# hv-supply.net
KiCad netlist of a schematic drawn in Altium Designer
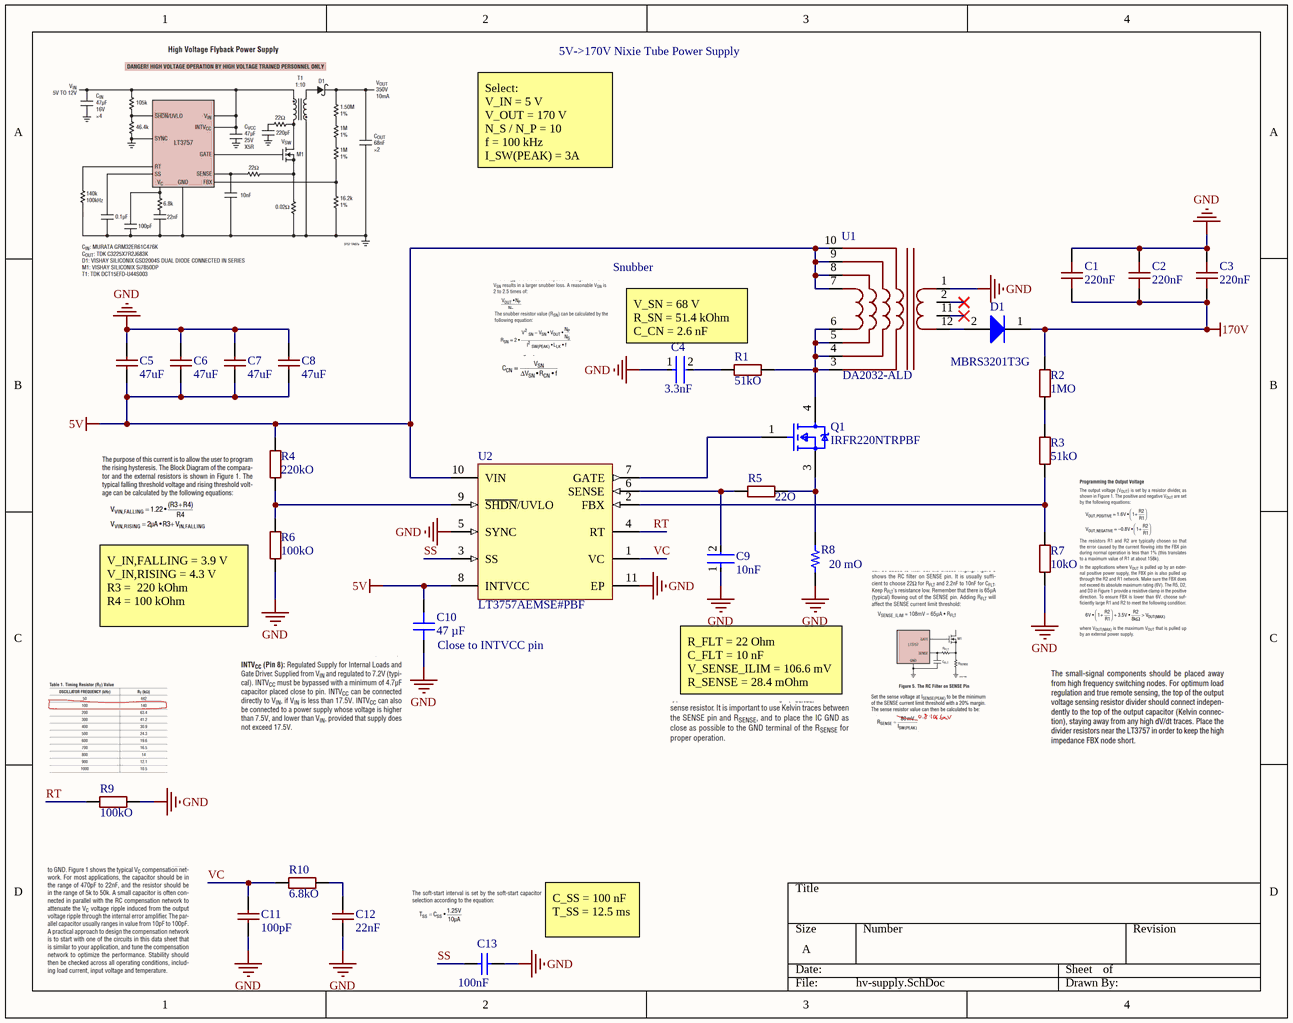
[diagram p0: hv-supply.SchDoc]

(export (version "E")
  (design (tool "Eeschema 10.0.6"))
  (components
    (comp (ref "C1")
      (value "220nF")
      (footprint "1206B224K251NT")
      (fields
        (field (name "JLCPCB PART #") "C1322383")
        (field (name "MANUFACTURER PART NUMBER") "1206B224K251NT")
        (field (name "MANUFACTURER") "FH (Guangdong Fenghua Advanced Tech)")
      )
      (libsource (lib "1206B224K251NT") (part "1206B224K251NT"))
    )
    (comp (ref "C2")
      (value "220nF")
      (footprint "1206B224K251NT")
      (fields
        (field (name "JLCPCB PART #") "C1322383")
        (field (name "MANUFACTURER PART NUMBER") "1206B224K251NT")
        (field (name "MANUFACTURER") "FH (Guangdong Fenghua Advanced Tech)")
      )
      (libsource (lib "1206B224K251NT") (part "1206B224K251NT"))
    )
    (comp (ref "C3")
      (value "220nF")
      (footprint "1206B224K251NT")
      (fields
        (field (name "JLCPCB PART #") "C1322383")
        (field (name "MANUFACTURER PART NUMBER") "1206B224K251NT")
        (field (name "MANUFACTURER") "FH (Guangdong Fenghua Advanced Tech)")
      )
      (libsource (lib "1206B224K251NT") (part "1206B224K251NT"))
    )
    (comp (ref "C4")
      (value "CL05B332KB5NNNC")
      (footprint "FP-CL388-IPC_C")
      (description "Cap Ceramic 3.3nF 50V X7R ±10% SMD 0402 +125°C Paper T/R")
      (fields
        (field (name "TOLERANCE") "10%")
        (field (name "CAPACITANCE") "3.3nF")
        (field (name "VOLTAGE") "50V")
      )
      (libsource (lib "Altium Content Vault") (part "b4654b650e69147ec39a6b967a45e02"))
    )
    (comp (ref "C5")
      (value "47uF")
      (footprint "CL21A476MQYNNNE")
      (fields
        (field (name "JLCPCB PART #") "C16780")
        (field (name "MANUFACTURER PART NUMBER") "CL21A476MQYNNNE")
        (field (name "MANUFACTURER") "Samsung Electro-Mechanics")
      )
      (libsource (lib "CL21A476MQYNNNE") (part "CL21A476MQYNNNE"))
    )
    (comp (ref "C6")
      (value "47uF")
      (footprint "CL21A476MQYNNNE")
      (fields
        (field (name "JLCPCB PART #") "C16780")
        (field (name "MANUFACTURER PART NUMBER") "CL21A476MQYNNNE")
        (field (name "MANUFACTURER") "Samsung Electro-Mechanics")
      )
      (libsource (lib "CL21A476MQYNNNE") (part "CL21A476MQYNNNE"))
    )
    (comp (ref "C7")
      (value "47uF")
      (footprint "CL21A476MQYNNNE")
      (fields
        (field (name "JLCPCB PART #") "C16780")
        (field (name "MANUFACTURER PART NUMBER") "CL21A476MQYNNNE")
        (field (name "MANUFACTURER") "Samsung Electro-Mechanics")
      )
      (libsource (lib "CL21A476MQYNNNE") (part "CL21A476MQYNNNE"))
    )
    (comp (ref "C8")
      (value "47uF")
      (footprint "CL21A476MQYNNNE")
      (fields
        (field (name "JLCPCB PART #") "C16780")
        (field (name "MANUFACTURER PART NUMBER") "CL21A476MQYNNNE")
        (field (name "MANUFACTURER") "Samsung Electro-Mechanics")
      )
      (libsource (lib "CL21A476MQYNNNE") (part "CL21A476MQYNNNE"))
    )
    (comp (ref "C9")
      (value "CL05B103KB5NNNC")
      (footprint "FP-CL165-IPC_C")
      (description "Cap Ceramic 10nF 50V X7R ±10% SMD 0402 +125°C Paper T/R")
      (fields
        (field (name "VOLTAGE") "50V")
        (field (name "TOLERANCE") "10%")
        (field (name "CAPACITANCE") "10nF")
      )
      (libsource (lib "Altium Content Vault") (part "b4654b650e69147ec39a6b967a45e02"))
    )
    (comp (ref "C10")
      (value "CL21A476MQYNNNE")
      (footprint "CAP 0805_2012")
      (description "CAP CER 47UF 6.3V X5R 0805")
      (fields
        (field (name "CAPACITANCE") "47 µF")
        (field (name "MANUFACTURER") "Samsung Electro-Mechanics")
        (field (name "TOLERANCE") "±20%")
      )
      (libsource (lib "Celestial Altium Library - altium_library") (part "Capacitor"))
    )
    (comp (ref "C11")
      (value "100pF")
      (footprint "0402CG101J500NT")
      (fields
        (field (name "JLCPCB PART #") "C1546")
        (field (name "MANUFACTURER PART NUMBER") "0402CG101J500NT")
        (field (name "MANUFACTURER") "FH (Guangdong Fenghua Advanced Tech)")
      )
      (libsource (lib "0402CG101J500NT") (part "0402CG101J500NT"))
    )
    (comp (ref "C12")
      (value "22nF")
      (footprint "0402B223K500NT")
      (fields
        (field (name "JLCPCB PART #") "C1532")
        (field (name "MANUFACTURER PART NUMBER") "0402B223K500NT")
        (field (name "MANUFACTURER") "FH (Guangdong Fenghua Advanced Tech)")
      )
      (libsource (lib "0402B223K500NT") (part "0402B223K500NT"))
    )
    (comp (ref "C13")
      (value "CL05B104KO5NNNC")
      (footprint "CAPC1050X55X23ML05T13")
      (description "Chip Capacitor, 100 nF, +/- 10%, 16 V, -55 to 125 degC, 0402 (1005 Metric), RoHS, Tape and Reel")
      (fields (field (name "MANUFACTURER") "Samsung Electro-Mechanics") (field (name "CAPACITANCE") "100nF"))
      (libsource (lib "Altium Content Vault") (part "CAP-NP-2"))
    )
    (comp (ref "D1")
      (value "MBRS3201T3G")
      (footprint "ONSC-SMC-2-403-03_V")
      (description "200 V, 3 A Schottky Fast Soft-Recovery Power Rectifier, 2-Pin SMC, Pb-Free, Tape and Reel")
      (fields (field (name "MANUFACTURER") "On Semiconductor"))
      (libsource (lib "Altium Content Vault") (part "ONSC-D-K1A2-2"))
    )
    (comp (ref "Q1")
      (value "IRFR220NTRPBF")
      (footprint "FP-PG-TO252-3-MFG")
      (description "MOSFET N-CH 200V 5A DPAK")
      (fields
        (field (name "MANUFACTURER") "Infineon")
        (field (name "OCTOPART") "https://octopart.com/irfr220ntrpbf-infineon-65874086")
      )
      (libsource (lib "Altium Content Vault") (part "2f21c11e83d30f418bb422e5a3b3d11"))
    )
    (comp (ref "R1")
      (value "51kO")
      (footprint "0402WGF5102TCE")
      (fields
        (field (name "JLCPCB PART #") "C25794")
        (field (name "MANUFACTURER PART NUMBER") "0402WGF5102TCE")
        (field (name "MANUFACTURER") "UNI-ROYAL(Uniroyal Elec)")
      )
      (libsource (lib "") (part "0402WGF5102TCE_1"))
    )
    (comp (ref "R2")
      (value "1MO")
      (footprint "0402WGF1004TCE")
      (fields
        (field (name "JLCPCB PART #") "C26083")
        (field (name "MANUFACTURER PART NUMBER") "0402WGF1004TCE")
        (field (name "MANUFACTURER") "UNI-ROYAL(Uniroyal Elec)")
      )
      (libsource (lib "0402WGF1004TCE") (part "0402WGF1004TCE"))
    )
    (comp (ref "R3")
      (value "51kO")
      (footprint "0402WGF5102TCE")
      (fields
        (field (name "JLCPCB PART #") "C25794")
        (field (name "MANUFACTURER PART NUMBER") "0402WGF5102TCE")
        (field (name "MANUFACTURER") "UNI-ROYAL(Uniroyal Elec)")
      )
      (libsource (lib "0402WGF5102TCE") (part "0402WGF5102TCE"))
    )
    (comp (ref "R4")
      (value "220kO")
      (footprint "0603WAF2203T5E")
      (fields
        (field (name "JLCPCB PART #") "C22961")
        (field (name "MANUFACTURER PART NUMBER") "0603WAF2203T5E")
        (field (name "MANUFACTURER") "UNI-ROYAL(Uniroyal Elec)")
      )
      (libsource (lib "0603WAF2203T5E") (part "0603WAF2203T5E"))
    )
    (comp (ref "R5")
      (value "22O")
      (footprint "0402WGF220JTCE")
      (fields
        (field (name "JLCPCB PART #") "C25092")
        (field (name "MANUFACTURER PART NUMBER") "0402WGF220JTCE")
        (field (name "MANUFACTURER") "UNI-ROYAL(Uniroyal Elec)")
      )
      (libsource (lib "0402WGF220JTCE") (part "0402WGF220JTCE"))
    )
    (comp (ref "R6")
      (value "100kO")
      (footprint "0402WGF1003TCE")
      (fields
        (field (name "JLCPCB PART #") "C25741")
        (field (name "MANUFACTURER PART NUMBER") "0402WGF1003TCE")
        (field (name "MANUFACTURER") "UNI-ROYAL(Uniroyal Elec)")
      )
      (libsource (lib "0402WGF1003TCE") (part "0402WGF1003TCE"))
    )
    (comp (ref "R7")
      (value "10kO")
      (footprint "0402WGF1002TCE")
      (fields
        (field (name "JLCPCB PART #") "C25744")
        (field (name "MANUFACTURER PART NUMBER") "0402WGF1002TCE")
        (field (name "MANUFACTURER") "UNI-ROYAL(Uniroyal Elec)")
      )
      (libsource (lib "0402WGF1002TCE") (part "0402WGF1002TCE"))
    )
    (comp (ref "R8")
      (value "PE0402FRF070R02L")
      (footprint "RES 0402_1005")
      (description "RES 0.02 OHM 1% 1/16W 0402")
      (fields
        (field (name "MANUFACTURER") "Yageo")
        (field (name "RESISTANCE") "20 mO")
        (field (name "TOLERANCE") "±1%")
      )
      (libsource (lib "Celestial Altium Library - altium_library") (part "Resistor"))
    )
    (comp (ref "R9")
      (value "100kO")
      (footprint "0402WGF1003TCE")
      (fields
        (field (name "JLCPCB PART #") "C25741")
        (field (name "MANUFACTURER PART NUMBER") "0402WGF1003TCE")
        (field (name "MANUFACTURER") "UNI-ROYAL(Uniroyal Elec)")
      )
      (libsource (lib "") (part "0402WGF1003TCE_1"))
    )
    (comp (ref "R10")
      (value "6.8kO")
      (footprint "0402WGF6801TCE")
      (fields
        (field (name "JLCPCB PART #") "C25917")
        (field (name "MANUFACTURER PART NUMBER") "0402WGF6801TCE")
        (field (name "MANUFACTURER") "UNI-ROYAL(Uniroyal Elec)")
      )
      (libsource (lib "0402WGF6801TCE") (part "0402WGF6801TCE"))
    )
    (comp (ref "U1")
      (value "DA2032-ALD")
      (footprint "DA2032-ALD")
      (description "Audio Transformers. SMD-12 Audio Transformers ROHS")
      (fields (field (name "JLCPCB PART #") "C7938441") (field (name "MANUFACTURER") "Coilcraft"))
      (libsource (lib "DA2032-ALD") (part "DA2032-ALD"))
    )
    (comp (ref "U2")
      (value "LT3757AEMSE#PBF")
      (footprint "LT-MSE-10-EDP_N")
      (fields (field (name "MANUFACTURER") "Linear Technology"))
      (libsource (lib "Altium Content Vault") (part "LT-LT375XA-X-10"))
    )
  )
  (nets
    (net (code "1") (name "/RT") (class "Default")
      (node (ref "R9") (pin "2") (pinfunction "2_2") (pintype "passive"))
      (node (ref "U2") (pin "4") (pinfunction "RT_4") (pintype "passive"))
    )
    (net (code "2") (name "/SS") (class "Default")
      (node (ref "C13") (pin "1") (pinfunction "1_1") (pintype "passive"))
      (node (ref "U2") (pin "3") (pinfunction "SS_3") (pintype "input"))
    )
    (net (code "3") (name "/VC") (class "Default")
      (node (ref "C11") (pin "2") (pinfunction "2_2") (pintype "passive"))
      (node (ref "R10") (pin "1") (pinfunction "1_1") (pintype "passive"))
      (node (ref "U2") (pin "1") (pinfunction "VC_1") (pintype "passive"))
    )
    (net (code "4") (name "5V") (class "Default")
      (node (ref "C10") (pin "2") (pinfunction "2_2") (pintype "passive"))
      (node (ref "C5") (pin "1") (pinfunction "1_1") (pintype "passive"))
      (node (ref "C6") (pin "1") (pinfunction "1_1") (pintype "passive"))
      (node (ref "C7") (pin "1") (pinfunction "1_1") (pintype "passive"))
      (node (ref "C8") (pin "1") (pinfunction "1_1") (pintype "passive"))
      (node (ref "R4") (pin "2") (pinfunction "2_2") (pintype "passive"))
      (node (ref "U1") (pin "10") (pinfunction "10_10") (pintype "passive"))
      (node (ref "U1") (pin "7") (pinfunction "7_7") (pintype "passive"))
      (node (ref "U1") (pin "8") (pinfunction "8_8") (pintype "passive"))
      (node (ref "U1") (pin "9") (pinfunction "9_9") (pintype "passive"))
      (node (ref "U2") (pin "10") (pinfunction "VIN_10") (pintype "power_in"))
      (node (ref "U2") (pin "8") (pinfunction "INTVCC_8") (pintype "power_in"))
    )
    (net (code "5") (name "170V") (class "Default")
      (node (ref "C1") (pin "2") (pinfunction "2_2") (pintype "passive"))
      (node (ref "C2") (pin "2") (pinfunction "2_2") (pintype "passive"))
      (node (ref "C3") (pin "2") (pinfunction "2_2") (pintype "passive"))
      (node (ref "D1") (pin "1") (pinfunction "K_1") (pintype "passive"))
      (node (ref "R2") (pin "2") (pinfunction "2_2") (pintype "passive"))
    )
    (net (code "6") (name "GND") (class "Default")
      (node (ref "C1") (pin "1") (pinfunction "1_1") (pintype "passive"))
      (node (ref "C10") (pin "1") (pinfunction "1_1") (pintype "passive"))
      (node (ref "C11") (pin "1") (pinfunction "1_1") (pintype "passive"))
      (node (ref "C12") (pin "1") (pinfunction "1_1") (pintype "passive"))
      (node (ref "C13") (pin "2") (pinfunction "2_2") (pintype "passive"))
      (node (ref "C2") (pin "1") (pinfunction "1_1") (pintype "passive"))
      (node (ref "C3") (pin "1") (pinfunction "1_1") (pintype "passive"))
      (node (ref "C4") (pin "1") (pinfunction "1_1") (pintype "passive"))
      (node (ref "C5") (pin "2") (pinfunction "2_2") (pintype "passive"))
      (node (ref "C6") (pin "2") (pinfunction "2_2") (pintype "passive"))
      (node (ref "C7") (pin "2") (pinfunction "2_2") (pintype "passive"))
      (node (ref "C8") (pin "2") (pinfunction "2_2") (pintype "passive"))
      (node (ref "C9") (pin "1") (pinfunction "1_1") (pintype "passive"))
      (node (ref "R6") (pin "1") (pinfunction "1_1") (pintype "passive"))
      (node (ref "R7") (pin "1") (pinfunction "1_1") (pintype "passive"))
      (node (ref "R8") (pin "1") (pinfunction "1_1") (pintype "passive"))
      (node (ref "R9") (pin "1") (pinfunction "1_1") (pintype "passive"))
      (node (ref "U1") (pin "1") (pinfunction "1_1") (pintype "passive"))
      (node (ref "U2") (pin "11") (pinfunction "EP_11") (pintype "power_in"))
      (node (ref "U2") (pin "5") (pinfunction "SYNC_5") (pintype "input"))
    )
    (net (code "7") (name "Net-(C4-Pad2)") (class "Default")
      (node (ref "C4") (pin "2") (pinfunction "2_2") (pintype "passive"))
      (node (ref "R1") (pin "2") (pinfunction "2_2") (pintype "passive"))
    )
    (net (code "8") (name "Net-(C12-Pad2)") (class "Default")
      (node (ref "C12") (pin "2") (pinfunction "2_2") (pintype "passive"))
      (node (ref "R10") (pin "2") (pinfunction "2_2") (pintype "passive"))
    )
    (net (code "9") (name "Net-(D1-A)") (class "Default")
      (node (ref "D1") (pin "2") (pinfunction "A_2") (pintype "passive"))
      (node (ref "U1") (pin "12") (pinfunction "12_12") (pintype "passive"))
    )
    (net (code "10") (name "Net-(Q1-DRAIN)") (class "Default")
      (node (ref "Q1") (pin "4") (pinfunction "DRAIN_4") (pintype "passive"))
      (node (ref "R1") (pin "1") (pinfunction "1_1") (pintype "passive"))
      (node (ref "U1") (pin "3") (pinfunction "3_3") (pintype "passive"))
      (node (ref "U1") (pin "4") (pinfunction "4_4") (pintype "passive"))
      (node (ref "U1") (pin "5") (pinfunction "5_5") (pintype "passive"))
      (node (ref "U1") (pin "6") (pinfunction "6_6") (pintype "passive"))
    )
    (net (code "11") (name "Net-(Q1-GATE)") (class "Default")
      (node (ref "Q1") (pin "1") (pinfunction "GATE_1") (pintype "passive"))
      (node (ref "U2") (pin "7") (pinfunction "GATE_7") (pintype "output"))
    )
    (net (code "12") (name "Net-(Q1-SOURCE)") (class "Default")
      (node (ref "Q1") (pin "3") (pinfunction "SOURCE_3") (pintype "passive"))
      (node (ref "R5") (pin "2") (pinfunction "2_2") (pintype "passive"))
      (node (ref "R8") (pin "2") (pinfunction "2_2") (pintype "passive"))
    )
    (net (code "13") (name "Net-(R2-Pad1)") (class "Default")
      (node (ref "R2") (pin "1") (pinfunction "1_1") (pintype "passive"))
      (node (ref "R3") (pin "2") (pinfunction "2_2") (pintype "passive"))
    )
    (net (code "14") (name "Net-(U2-FBX)") (class "Default")
      (node (ref "R3") (pin "1") (pinfunction "1_1") (pintype "passive"))
      (node (ref "R7") (pin "2") (pinfunction "2_2") (pintype "passive"))
      (node (ref "U2") (pin "2") (pinfunction "FBX_2") (pintype "input"))
    )
    (net (code "15") (name "Net-(U2-SENSE)") (class "Default")
      (node (ref "C9") (pin "2") (pinfunction "2_2") (pintype "passive"))
      (node (ref "R5") (pin "1") (pinfunction "1_1") (pintype "passive"))
      (node (ref "U2") (pin "6") (pinfunction "SENSE_6") (pintype "input"))
    )
    (net (code "16") (name "Net-(U2-~{SHDN}{slash}UVLO)") (class "Default")
      (node (ref "R4") (pin "1") (pinfunction "1_1") (pintype "passive"))
      (node (ref "R6") (pin "2") (pinfunction "2_2") (pintype "passive"))
      (node (ref "U2") (pin "9") (pinfunction "~{SHDN}/UVLO_9") (pintype "input"))
    )
    (net (code "17") (name "unconnected-(U1-Pad2)") (class "Default")
      (node (ref "U1") (pin "2") (pinfunction "2_2") (pintype "passive+no_connect"))
    )
    (net (code "18") (name "unconnected-(U1-Pad11)") (class "Default")
      (node (ref "U1") (pin "11") (pinfunction "11_11") (pintype "passive+no_connect"))
    )
  )
)
